# EVK-NORA-B2_SCHEM_0006_USBhub_FTDI.net
KiCad netlist of a schematic drawn in Altium Designer
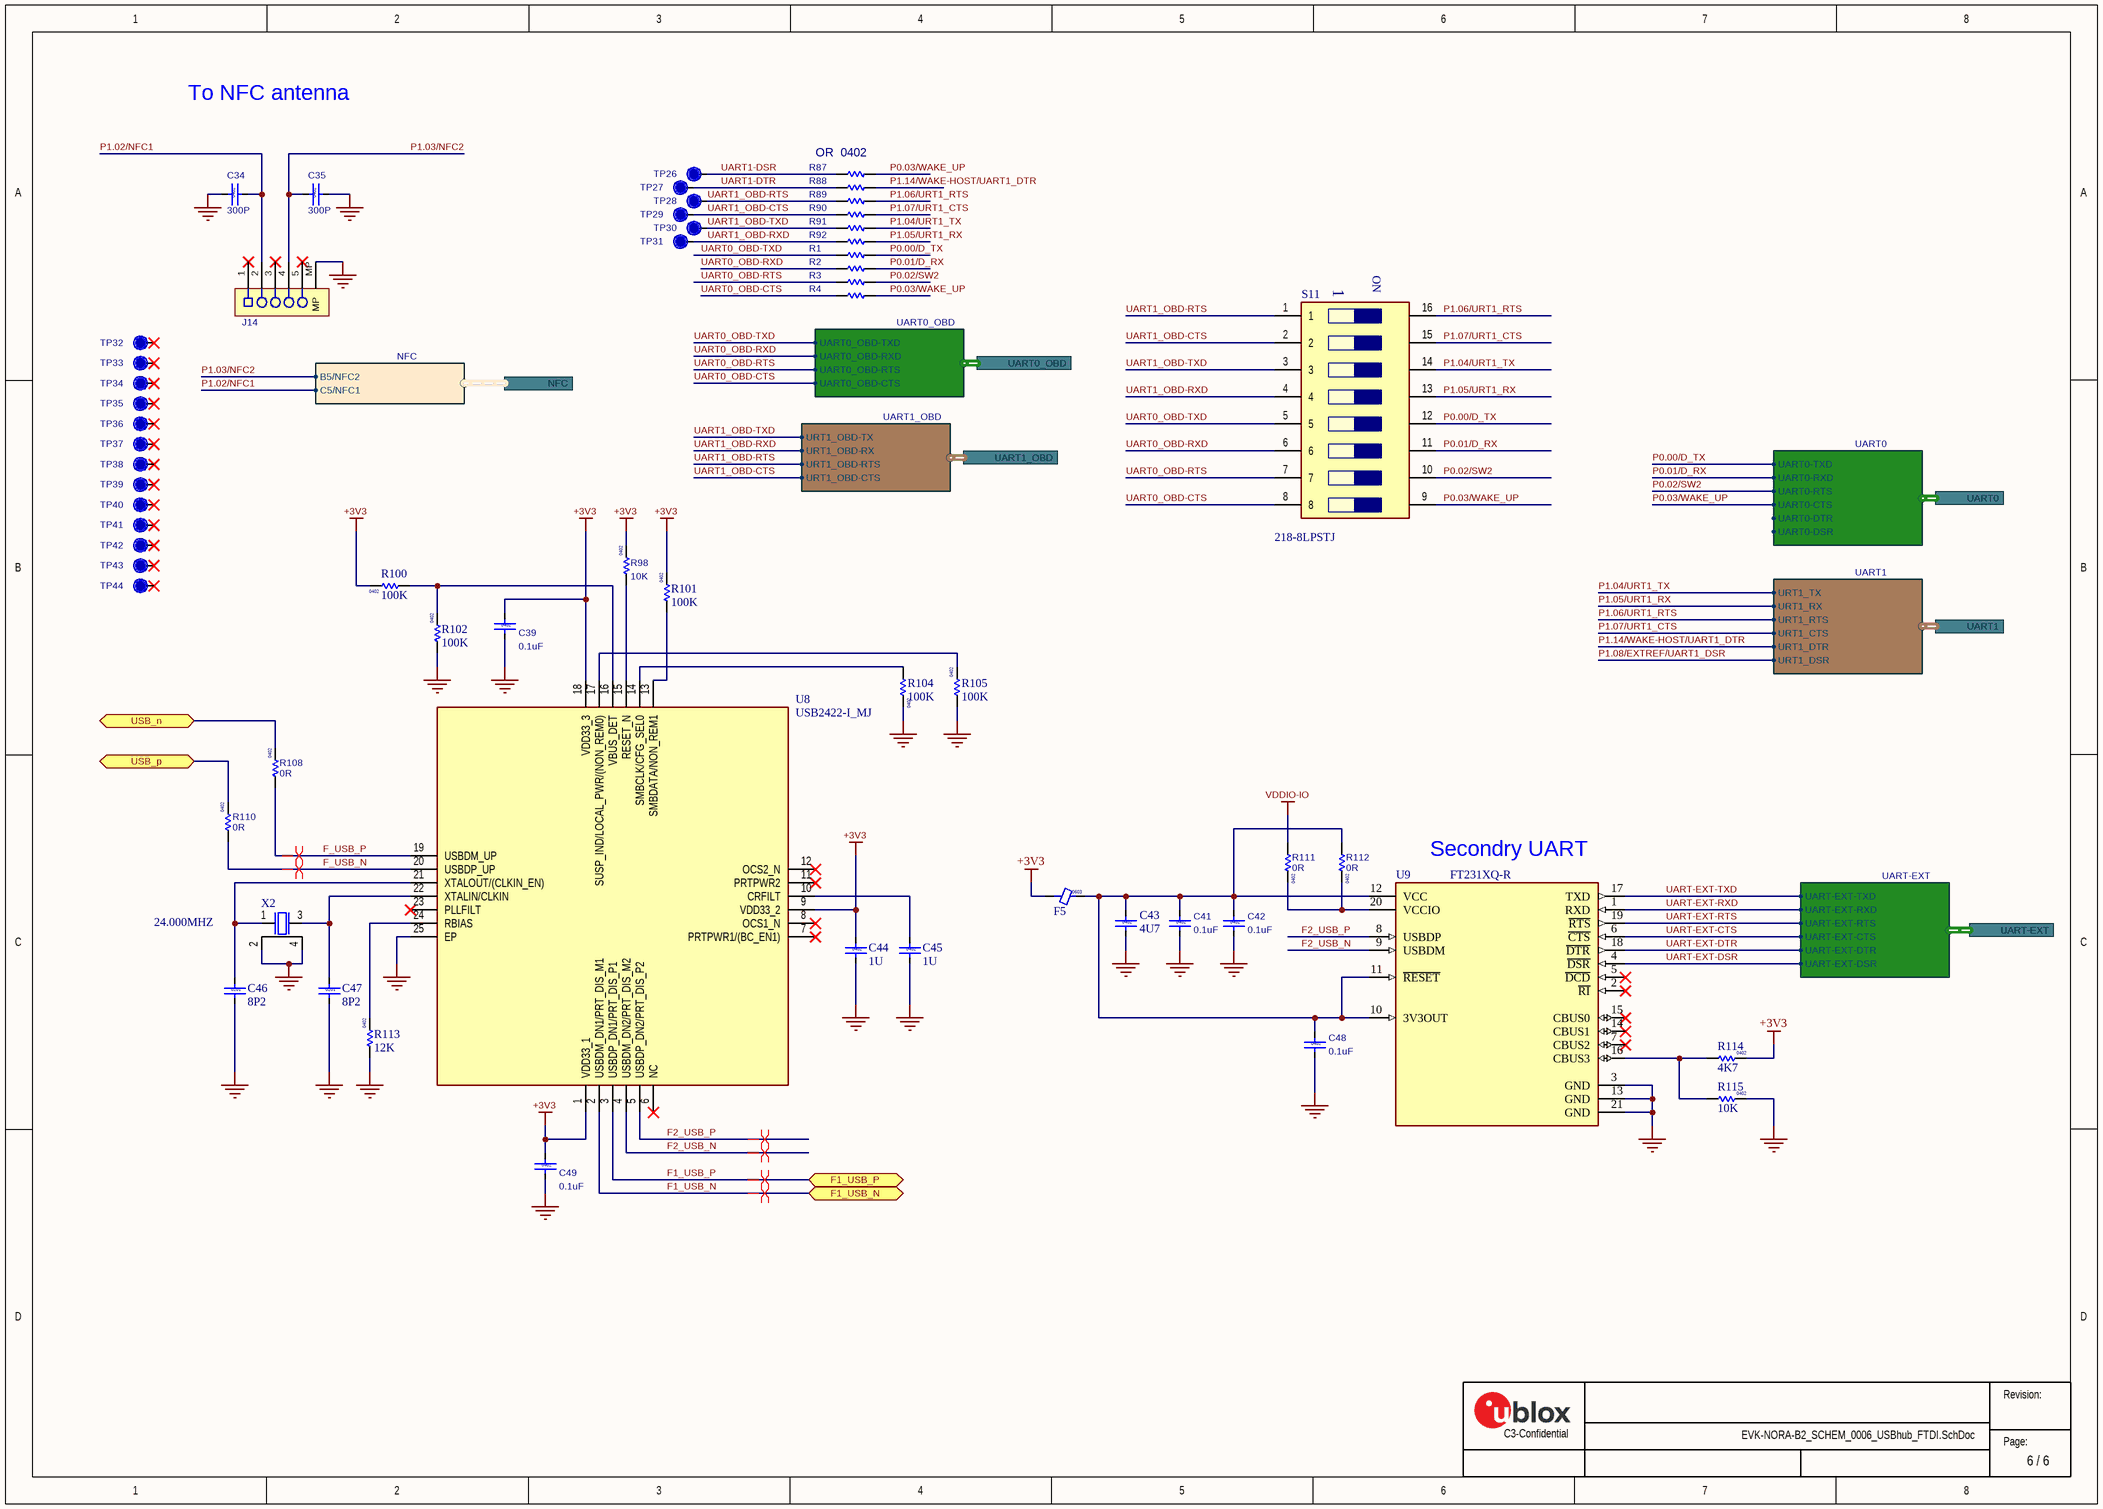
[diagram p0: EVK-NORA-B2_SCHEM_0006_USBhub_FTDI.SchDoc]

(export (version "E")
  (design (tool "Eeschema 10.0.6"))
  (components
    (comp (ref "C34")
      (value "300P")
      (footprint "Cap 0402 HD")
      (description "CAP CER C0G 0402 300P 50V")
      (fields
        (field (name "SIZE") "0402")
        (field (name "PART NUMBER") "UBXH01-0000594")
        (field (name "MANUFACTURER") "Murata Manufacturing Company, Ltd.")
        (field (name "EDITOR") "eric.moog")
      )
      (libsource (lib "UBX_Parts_DB_Lib") (part "Cap Chip"))
    )
    (comp (ref "C35")
      (value "300P")
      (footprint "Cap 0402 HD")
      (description "CAP CER C0G 0402 300P 50V")
      (fields
        (field (name "SIZE") "0402")
        (field (name "PART NUMBER") "UBXH01-0000594")
        (field (name "MANUFACTURER") "Murata Manufacturing Company, Ltd.")
        (field (name "EDITOR") "eric.moog")
      )
      (libsource (lib "UBX_Parts_DB_Lib") (part "Cap Chip"))
    )
    (comp (ref "C39")
      (value "0.1uF")
      (footprint "Cap 0402 HD")
      (description "Cap, Ceramic 0.1uF 10V 10% X5R 0402")
      (fields
        (field (name "SIZE") "0402")
        (field (name "PART NUMBER") "120-00016")
        (field (name "MANUFACTURER") "Murata Electronics North America")
      )
      (libsource (lib "Arena_Parts_DB_Lib") (part "Cap Chip"))
    )
    (comp (ref "C41")
      (value "0.1uF")
      (footprint "Cap 0402 HD")
      (description "Cap, Ceramic 0.1uF 10V 10% X5R 0402")
      (fields
        (field (name "SIZE") "0402")
        (field (name "PART NUMBER") "120-00016")
        (field (name "MANUFACTURER") "Murata Electronics North America")
      )
      (libsource (lib "Arena_Parts_DB_Lib") (part "Cap Chip"))
    )
    (comp (ref "C42")
      (value "0.1uF")
      (footprint "Cap 0402 HD")
      (description "Cap, Ceramic 0.1uF 10V 10% X5R 0402")
      (fields
        (field (name "SIZE") "0402")
        (field (name "PART NUMBER") "120-00016")
        (field (name "MANUFACTURER") "Murata Electronics North America")
      )
      (libsource (lib "Arena_Parts_DB_Lib") (part "Cap Chip"))
    )
    (comp (ref "C43")
      (value "4U7")
      (footprint "Cap 0402 HD")
      (description "CAP CER X5R 0402 4U7 20% 10V")
      (fields
        (field (name "SIZE") "0402")
        (field (name "PART NUMBER") "UBXH01-0000243")
        (field (name "TOLERANCE") "20%")
        (field (name "EDITOR") "martin.pilik")
        (field (name "RELEASED BY") "fabrice.bret-dibat")
      )
      (libsource (lib "UBX_Parts_DB_Lib") (part "Cap Chip"))
    )
    (comp (ref "C44")
      (value "1U")
      (footprint "Cap 0402 HD")
      (description "CAP CER X5R 0402 1U 10% 10V")
      (fields
        (field (name "SIZE") "0402")
        (field (name "PART NUMBER") "UBXH01-0000248")
        (field (name "TOLERANCE") "10%")
        (field (name "EDITOR") "michael.hein")
        (field (name "RELEASED BY") "igor.shevchenko")
      )
      (libsource (lib "UBX_Parts_DB_Lib") (part "Cap Chip"))
    )
    (comp (ref "C45")
      (value "1U")
      (footprint "Cap 0402 HD")
      (description "CAP CER X5R 0402 1U 10% 10V")
      (fields
        (field (name "SIZE") "0402")
        (field (name "PART NUMBER") "UBXH01-0000248")
        (field (name "TOLERANCE") "10%")
        (field (name "EDITOR") "michael.hein")
        (field (name "RELEASED BY") "igor.shevchenko")
      )
      (libsource (lib "UBX_Parts_DB_Lib") (part "Cap Chip"))
    )
    (comp (ref "C46")
      (value "8P2")
      (footprint "Cap 0201 HD")
      (description "CAP CER C0G 0201 8P2 +/-0.5P 25V")
      (fields
        (field (name "SIZE") "0201")
        (field (name "PART NUMBER") "UBXH01-0013002")
        (field (name "TOLERANCE") "+/-0.5P")
        (field (name "EDITOR") "roland.rust")
        (field (name "RELEASED BY") "roland.rust")
      )
      (libsource (lib "UBX_Parts_DB_Lib") (part "Cap Chip"))
    )
    (comp (ref "C47")
      (value "8P2")
      (footprint "Cap 0201 HD")
      (description "CAP CER C0G 0201 8P2 +/-0.5P 25V")
      (fields
        (field (name "SIZE") "0201")
        (field (name "PART NUMBER") "UBXH01-0013002")
        (field (name "TOLERANCE") "+/-0.5P")
        (field (name "EDITOR") "roland.rust")
        (field (name "RELEASED BY") "roland.rust")
      )
      (libsource (lib "UBX_Parts_DB_Lib") (part "Cap Chip"))
    )
    (comp (ref "C48")
      (value "0.1uF")
      (footprint "Cap 0402 HD")
      (description "Cap, Ceramic 0.1uF 10V 10% X5R 0402")
      (fields
        (field (name "SIZE") "0402")
        (field (name "PART NUMBER") "120-00016")
        (field (name "MANUFACTURER") "Murata Electronics North America")
      )
      (libsource (lib "Arena_Parts_DB_Lib") (part "Cap Chip"))
    )
    (comp (ref "C49")
      (value "0.1uF")
      (footprint "Cap 0402 HD")
      (description "Cap, Ceramic 0.1uF 10V 10% X5R 0402")
      (fields
        (field (name "SIZE") "0402")
        (field (name "PART NUMBER") "120-00016")
        (field (name "MANUFACTURER") "Murata Electronics North America")
      )
      (libsource (lib "Arena_Parts_DB_Lib") (part "Cap Chip"))
    )
    (comp (ref "F5")
      (value "UBXH08-0000001")
      (footprint "IND_0603_1750Lx950Wx1050H_600x800Pad_800G_FLX")
      (description "FERRITE BEAD 0603 600 OHM AT 100MHZ 600OHM 500mA")
      (fields
        (field (name "SIZE") "0603")
        (field (name "MANUFACTURER") "TDK Corporation")
        (field (name "EDITOR") "daniel.hurni")
        (field (name "RELEASED BY") "martin.frauchiger")
      )
      (libsource (lib "UBX_Parts_DB_Lib") (part "FB sm"))
    )
    (comp (ref "J14")
      (value "UBXH04-0000798")
      (footprint "AVX/Kyocera - 046284005001846")
      (description "0.50MM PITCH SMD RA FFC FPC CONN 5 -PIN 50V 400mA")
      (fields
        (field (name "VOLTAGE") "50V")
        (field (name "MANUFACTURER") "AVX")
        (field (name "EDITOR") "eric.moog")
      )
      (libsource (lib "UBX_Parts_DB_Lib") (part "CON-5Pin_1Row-046284005001846"))
    )
    (comp (ref "R1")
      (value "UBXH18-00030020R")
      (footprint "RES 0402 HD")
      (description "RES THICK FILM CHIP 0402 0R 0 100mW")
      (fields
        (field (name "PART NUMBER") "UBXH18-0003002")
        (field (name "TOLERANCE") "0")
        (field (name "EDITOR") "charlotte.biber")
        (field (name "RELEASED BY") "peter.mueller")
      )
      (libsource (lib "UBX_Parts_DB_Lib") (part "Res sm"))
    )
    (comp (ref "R2")
      (value "UBXH18-00030020R")
      (footprint "RES 0402 HD")
      (description "RES THICK FILM CHIP 0402 0R 0 100mW")
      (fields
        (field (name "PART NUMBER") "UBXH18-0003002")
        (field (name "TOLERANCE") "0")
        (field (name "EDITOR") "charlotte.biber")
        (field (name "RELEASED BY") "peter.mueller")
      )
      (libsource (lib "UBX_Parts_DB_Lib") (part "Res sm"))
    )
    (comp (ref "R3")
      (value "UBXH18-00030020R")
      (footprint "RES 0402 HD")
      (description "RES THICK FILM CHIP 0402 0R 0 100mW")
      (fields
        (field (name "PART NUMBER") "UBXH18-0003002")
        (field (name "TOLERANCE") "0")
        (field (name "EDITOR") "charlotte.biber")
        (field (name "RELEASED BY") "peter.mueller")
      )
      (libsource (lib "UBX_Parts_DB_Lib") (part "Res sm"))
    )
    (comp (ref "R4")
      (value "UBXH18-00030020R")
      (footprint "RES 0402 HD")
      (description "RES THICK FILM CHIP 0402 0R 0 100mW")
      (fields
        (field (name "PART NUMBER") "UBXH18-0003002")
        (field (name "TOLERANCE") "0")
        (field (name "EDITOR") "charlotte.biber")
        (field (name "RELEASED BY") "peter.mueller")
      )
      (libsource (lib "UBX_Parts_DB_Lib") (part "Res sm"))
    )
    (comp (ref "R87")
      (value "UBXH18-00030020R")
      (footprint "RES 0402 HD")
      (description "RES THICK FILM CHIP 0402 0R 0 100mW")
      (fields
        (field (name "PART NUMBER") "UBXH18-0003002")
        (field (name "TOLERANCE") "0")
        (field (name "EDITOR") "charlotte.biber")
        (field (name "RELEASED BY") "peter.mueller")
      )
      (libsource (lib "UBX_Parts_DB_Lib") (part "Res sm"))
    )
    (comp (ref "R88")
      (value "UBXH18-00030020R")
      (footprint "RES 0402 HD")
      (description "RES THICK FILM CHIP 0402 0R 0 100mW")
      (fields
        (field (name "PART NUMBER") "UBXH18-0003002")
        (field (name "TOLERANCE") "0")
        (field (name "EDITOR") "charlotte.biber")
        (field (name "RELEASED BY") "peter.mueller")
      )
      (libsource (lib "UBX_Parts_DB_Lib") (part "Res sm"))
    )
    (comp (ref "R89")
      (value "UBXH18-00030020R")
      (footprint "RES 0402 HD")
      (description "RES THICK FILM CHIP 0402 0R 0 100mW")
      (fields
        (field (name "PART NUMBER") "UBXH18-0003002")
        (field (name "TOLERANCE") "0")
        (field (name "EDITOR") "charlotte.biber")
        (field (name "RELEASED BY") "peter.mueller")
      )
      (libsource (lib "UBX_Parts_DB_Lib") (part "Res sm"))
    )
    (comp (ref "R90")
      (value "UBXH18-00030020R")
      (footprint "RES 0402 HD")
      (description "RES THICK FILM CHIP 0402 0R 0 100mW")
      (fields
        (field (name "PART NUMBER") "UBXH18-0003002")
        (field (name "TOLERANCE") "0")
        (field (name "EDITOR") "charlotte.biber")
        (field (name "RELEASED BY") "peter.mueller")
      )
      (libsource (lib "UBX_Parts_DB_Lib") (part "Res sm"))
    )
    (comp (ref "R91")
      (value "UBXH18-00030020R")
      (footprint "RES 0402 HD")
      (description "RES THICK FILM CHIP 0402 0R 0 100mW")
      (fields
        (field (name "PART NUMBER") "UBXH18-0003002")
        (field (name "TOLERANCE") "0")
        (field (name "EDITOR") "charlotte.biber")
        (field (name "RELEASED BY") "peter.mueller")
      )
      (libsource (lib "UBX_Parts_DB_Lib") (part "Res sm"))
    )
    (comp (ref "R92")
      (value "UBXH18-00030020R")
      (footprint "RES 0402 HD")
      (description "RES THICK FILM CHIP 0402 0R 0 100mW")
      (fields
        (field (name "PART NUMBER") "UBXH18-0003002")
        (field (name "TOLERANCE") "0")
        (field (name "EDITOR") "charlotte.biber")
        (field (name "RELEASED BY") "peter.mueller")
      )
      (libsource (lib "UBX_Parts_DB_Lib") (part "Res sm"))
    )
    (comp (ref "R98")
      (value "10K")
      (footprint "RES 0402 HD")
      (description "RES THICK FILM CHIP 0402 10K 1% 63mW")
      (fields
        (field (name "SIZE") "0402")
        (field (name "PART NUMBER") "UBXH18-0000065")
        (field (name "TOLERANCE") "1%")
        (field (name "EDITOR") "erian.bezhani")
        (field (name "RELEASED BY") "massimo.vlacci")
      )
      (libsource (lib "UBX_Parts_DB_Lib") (part "Res sm"))
    )
    (comp (ref "R100")
      (value "100K")
      (footprint "RES 0402 HD")
      (description "RES THICK FILM CHIP 0402 100K 1% 63mW")
      (fields
        (field (name "SIZE") "0402")
        (field (name "PART NUMBER") "UBXH18-0000005")
        (field (name "TOLERANCE") "1%")
        (field (name "EDITOR") "dario.antonaz")
        (field (name "RELEASED BY") "sandro.sestan")
      )
      (libsource (lib "UBX_Parts_DB_Lib") (part "Res sm"))
    )
    (comp (ref "R101")
      (value "100K")
      (footprint "RES 0402 HD")
      (description "RES THICK FILM CHIP 0402 100K 1% 63mW")
      (fields
        (field (name "SIZE") "0402")
        (field (name "PART NUMBER") "UBXH18-0000005")
        (field (name "TOLERANCE") "1%")
        (field (name "EDITOR") "dario.antonaz")
        (field (name "RELEASED BY") "sandro.sestan")
      )
      (libsource (lib "UBX_Parts_DB_Lib") (part "Res sm"))
    )
    (comp (ref "R102")
      (value "100K")
      (footprint "RES 0402 HD")
      (description "RES THICK FILM CHIP 0402 100K 1% 63mW")
      (fields
        (field (name "SIZE") "0402")
        (field (name "PART NUMBER") "UBXH18-0000005")
        (field (name "TOLERANCE") "1%")
        (field (name "EDITOR") "dario.antonaz")
        (field (name "RELEASED BY") "sandro.sestan")
      )
      (libsource (lib "UBX_Parts_DB_Lib") (part "Res sm"))
    )
    (comp (ref "R104")
      (value "100K")
      (footprint "RES 0402 HD")
      (description "RES THICK FILM CHIP 0402 100K 1% 63mW")
      (fields
        (field (name "SIZE") "0402")
        (field (name "PART NUMBER") "UBXH18-0000005")
        (field (name "TOLERANCE") "1%")
        (field (name "EDITOR") "dario.antonaz")
        (field (name "RELEASED BY") "sandro.sestan")
      )
      (libsource (lib "UBX_Parts_DB_Lib") (part "Res sm"))
    )
    (comp (ref "R105")
      (value "100K")
      (footprint "RES 0402 HD")
      (description "RES THICK FILM CHIP 0402 100K 1% 63mW")
      (fields
        (field (name "SIZE") "0402")
        (field (name "PART NUMBER") "UBXH18-0000005")
        (field (name "TOLERANCE") "1%")
        (field (name "EDITOR") "dario.antonaz")
        (field (name "RELEASED BY") "sandro.sestan")
      )
      (libsource (lib "UBX_Parts_DB_Lib") (part "Res sm"))
    )
    (comp (ref "R108")
      (value "0R")
      (footprint "RES 0402 HD")
      (description "RES THICK FILM CHIP 0402 0R 0 100mW")
      (fields
        (field (name "SIZE") "0402")
        (field (name "PART NUMBER") "UBXH18-0003002")
        (field (name "TOLERANCE") "0")
        (field (name "EDITOR") "charlotte.biber")
        (field (name "RELEASED BY") "peter.mueller")
      )
      (libsource (lib "UBX_Parts_DB_Lib") (part "Res sm"))
    )
    (comp (ref "R110")
      (value "0R")
      (footprint "RES 0402 HD")
      (description "RES THICK FILM CHIP 0402 0R 0 100mW")
      (fields
        (field (name "SIZE") "0402")
        (field (name "PART NUMBER") "UBXH18-0003002")
        (field (name "TOLERANCE") "0")
        (field (name "EDITOR") "charlotte.biber")
        (field (name "RELEASED BY") "peter.mueller")
      )
      (libsource (lib "UBX_Parts_DB_Lib") (part "Res sm"))
    )
    (comp (ref "R111")
      (value "0R")
      (footprint "RES 0402 HD")
      (description "RES THICK FILM CHIP 0402 0R 0 100mW")
      (fields
        (field (name "SIZE") "0402")
        (field (name "PART NUMBER") "UBXH18-0003002")
        (field (name "TOLERANCE") "0")
        (field (name "EDITOR") "charlotte.biber")
        (field (name "RELEASED BY") "peter.mueller")
      )
      (libsource (lib "UBX_Parts_DB_Lib") (part "Res sm"))
    )
    (comp (ref "R112")
      (value "0R")
      (footprint "RES 0402 HD")
      (description "RES THICK FILM CHIP 0402 0R 0 100mW")
      (fields
        (field (name "SIZE") "0402")
        (field (name "PART NUMBER") "UBXH18-0003002")
        (field (name "TOLERANCE") "0")
        (field (name "EDITOR") "charlotte.biber")
        (field (name "RELEASED BY") "peter.mueller")
      )
      (libsource (lib "UBX_Parts_DB_Lib") (part "Res sm"))
    )
    (comp (ref "R113")
      (value "12K")
      (footprint "RES_0402_1100Lx600Wx400H_500x600Pad_400G_FLX")
      (description "RES THICK FILM CHIP 0402 12K 1% 62.5mW")
      (fields
        (field (name "SIZE") "0402")
        (field (name "PART NUMBER") "UBXH18-0000133")
        (field (name "TOLERANCE") "1%")
        (field (name "EDITOR") "pierpaolo.arban")
        (field (name "RELEASED BY") "dario.antonaz")
      )
      (libsource (lib "UBX_Parts_DB_Lib") (part "Res sm"))
    )
    (comp (ref "R114")
      (value "4K7")
      (footprint "RES_0402_1100Lx600Wx400H_500x600Pad_400G_FLX")
      (description "RES THICK FILM CHIP 0402 4K7 5% 100mW")
      (fields
        (field (name "SIZE") "0402")
        (field (name "PART NUMBER") "UBXH18-0008065")
        (field (name "TOLERANCE") "5%")
        (field (name "EDITOR") "martin.frauchiger")
        (field (name "RELEASED BY") "martin.frauchiger")
      )
      (libsource (lib "UBX_Parts_DB_Lib") (part "Res sm"))
    )
    (comp (ref "R115")
      (value "10K")
      (footprint "RES_0402_1100Lx600Wx400H_500x600Pad_400G_FLX")
      (description "RES THICK FILM CHIP 0402 10K 5% 100mW")
      (fields
        (field (name "SIZE") "0402")
        (field (name "PART NUMBER") "UBXH18-0008073")
        (field (name "TOLERANCE") "5%")
        (field (name "EDITOR") "martin.frauchiger")
        (field (name "RELEASED BY") "martin.frauchiger")
      )
      (libsource (lib "UBX_Parts_DB_Lib") (part "Res sm"))
    )
    (comp (ref "S11")
      (value "218-8LPSTJ")
      (footprint "2188LPSTJ")
      (description "Switch")
      (fields (field (name "MOUSER PART NUMBER") "774-2188LPSTJ"))
      (libsource (lib "SamacSys") (part "218-8LPSTJ"))
    )
    (comp (ref "TP26")
      (value "TP")
      (footprint "TP10R")
      (description "Testpoint, Round 1.0mm Dia")
      (fields
        (field (name "PART NUMBER") "TP10R")
        (field (name "ADDED BY") "Jeremy D")
        (field (name "CHECKED BY") "Paul B")
      )
      (libsource (lib "LEGACY_Rigado_AltiumLib") (part "TP_R"))
    )
    (comp (ref "TP27")
      (value "TP")
      (footprint "TP10R")
      (description "Testpoint, Round 1.0mm Dia")
      (fields
        (field (name "PART NUMBER") "TP10R")
        (field (name "ADDED BY") "Jeremy D")
        (field (name "CHECKED BY") "Paul B")
      )
      (libsource (lib "LEGACY_Rigado_AltiumLib") (part "TP_R"))
    )
    (comp (ref "TP28")
      (value "TP")
      (footprint "TP10R")
      (description "Testpoint, Round 1.0mm Dia")
      (fields
        (field (name "PART NUMBER") "TP10R")
        (field (name "ADDED BY") "Jeremy D")
        (field (name "CHECKED BY") "Paul B")
      )
      (libsource (lib "LEGACY_Rigado_AltiumLib") (part "TP_R"))
    )
    (comp (ref "TP29")
      (value "TP")
      (footprint "TP10R")
      (description "Testpoint, Round 1.0mm Dia")
      (fields
        (field (name "PART NUMBER") "TP10R")
        (field (name "ADDED BY") "Jeremy D")
        (field (name "CHECKED BY") "Paul B")
      )
      (libsource (lib "LEGACY_Rigado_AltiumLib") (part "TP_R"))
    )
    (comp (ref "TP30")
      (value "TP")
      (footprint "TP10R")
      (description "Testpoint, Round 1.0mm Dia")
      (fields
        (field (name "PART NUMBER") "TP10R")
        (field (name "ADDED BY") "Jeremy D")
        (field (name "CHECKED BY") "Paul B")
      )
      (libsource (lib "LEGACY_Rigado_AltiumLib") (part "TP_R"))
    )
    (comp (ref "TP31")
      (value "TP")
      (footprint "TP10R")
      (description "Testpoint, Round 1.0mm Dia")
      (fields
        (field (name "PART NUMBER") "TP10R")
        (field (name "ADDED BY") "Jeremy D")
        (field (name "CHECKED BY") "Paul B")
      )
      (libsource (lib "LEGACY_Rigado_AltiumLib") (part "TP_R"))
    )
    (comp (ref "TP32")
      (value "TP")
      (footprint "TP10R")
      (description "Testpoint, Round 1.0mm Dia")
      (fields
        (field (name "PART NUMBER") "TP10R")
        (field (name "ADDED BY") "Jeremy D")
        (field (name "CHECKED BY") "Paul B")
      )
      (libsource (lib "LEGACY_Rigado_AltiumLib") (part "TP_R"))
    )
    (comp (ref "TP33")
      (value "TP")
      (footprint "TP10R")
      (description "Testpoint, Round 1.0mm Dia")
      (fields
        (field (name "PART NUMBER") "TP10R")
        (field (name "ADDED BY") "Jeremy D")
        (field (name "CHECKED BY") "Paul B")
      )
      (libsource (lib "LEGACY_Rigado_AltiumLib") (part "TP_R"))
    )
    (comp (ref "TP34")
      (value "TP")
      (footprint "TP10R")
      (description "Testpoint, Round 1.0mm Dia")
      (fields
        (field (name "PART NUMBER") "TP10R")
        (field (name "ADDED BY") "Jeremy D")
        (field (name "CHECKED BY") "Paul B")
      )
      (libsource (lib "LEGACY_Rigado_AltiumLib") (part "TP_R"))
    )
    (comp (ref "TP35")
      (value "TP")
      (footprint "TP10R")
      (description "Testpoint, Round 1.0mm Dia")
      (fields
        (field (name "PART NUMBER") "TP10R")
        (field (name "ADDED BY") "Jeremy D")
        (field (name "CHECKED BY") "Paul B")
      )
      (libsource (lib "LEGACY_Rigado_AltiumLib") (part "TP_R"))
    )
    (comp (ref "TP36")
      (value "TP")
      (footprint "TP10R")
      (description "Testpoint, Round 1.0mm Dia")
      (fields
        (field (name "PART NUMBER") "TP10R")
        (field (name "ADDED BY") "Jeremy D")
        (field (name "CHECKED BY") "Paul B")
      )
      (libsource (lib "LEGACY_Rigado_AltiumLib") (part "TP_R"))
    )
    (comp (ref "TP37")
      (value "TP")
      (footprint "TP10R")
      (description "Testpoint, Round 1.0mm Dia")
      (fields
        (field (name "PART NUMBER") "TP10R")
        (field (name "ADDED BY") "Jeremy D")
        (field (name "CHECKED BY") "Paul B")
      )
      (libsource (lib "LEGACY_Rigado_AltiumLib") (part "TP_R"))
    )
    (comp (ref "TP38")
      (value "TP")
      (footprint "TP10R")
      (description "Testpoint, Round 1.0mm Dia")
      (fields
        (field (name "PART NUMBER") "TP10R")
        (field (name "ADDED BY") "Jeremy D")
        (field (name "CHECKED BY") "Paul B")
      )
      (libsource (lib "LEGACY_Rigado_AltiumLib") (part "TP_R"))
    )
    (comp (ref "TP39")
      (value "TP")
      (footprint "TP10R")
      (description "Testpoint, Round 1.0mm Dia")
      (fields
        (field (name "PART NUMBER") "TP10R")
        (field (name "ADDED BY") "Jeremy D")
        (field (name "CHECKED BY") "Paul B")
      )
      (libsource (lib "LEGACY_Rigado_AltiumLib") (part "TP_R"))
    )
    (comp (ref "TP40")
      (value "TP")
      (footprint "TP10R")
      (description "Testpoint, Round 1.0mm Dia")
      (fields
        (field (name "PART NUMBER") "TP10R")
        (field (name "ADDED BY") "Jeremy D")
        (field (name "CHECKED BY") "Paul B")
      )
      (libsource (lib "LEGACY_Rigado_AltiumLib") (part "TP_R"))
    )
    (comp (ref "TP41")
      (value "TP")
      (footprint "TP10R")
      (description "Testpoint, Round 1.0mm Dia")
      (fields
        (field (name "PART NUMBER") "TP10R")
        (field (name "ADDED BY") "Jeremy D")
        (field (name "CHECKED BY") "Paul B")
      )
      (libsource (lib "LEGACY_Rigado_AltiumLib") (part "TP_R"))
    )
    (comp (ref "TP42")
      (value "TP")
      (footprint "TP10R")
      (description "Testpoint, Round 1.0mm Dia")
      (fields
        (field (name "PART NUMBER") "TP10R")
        (field (name "ADDED BY") "Jeremy D")
        (field (name "CHECKED BY") "Paul B")
      )
      (libsource (lib "LEGACY_Rigado_AltiumLib") (part "TP_R"))
    )
    (comp (ref "TP43")
      (value "TP")
      (footprint "TP10R")
      (description "Testpoint, Round 1.0mm Dia")
      (fields
        (field (name "PART NUMBER") "TP10R")
        (field (name "ADDED BY") "Jeremy D")
        (field (name "CHECKED BY") "Paul B")
      )
      (libsource (lib "LEGACY_Rigado_AltiumLib") (part "TP_R"))
    )
    (comp (ref "TP44")
      (value "TP")
      (footprint "TP10R")
      (description "Testpoint, Round 1.0mm Dia")
      (fields
        (field (name "PART NUMBER") "TP10R")
        (field (name "ADDED BY") "Jeremy D")
        (field (name "CHECKED BY") "Paul B")
      )
      (libsource (lib "LEGACY_Rigado_AltiumLib") (part "TP_R"))
    )
    (comp (ref "U8")
      (value "USB2422-I_MJ")
      (footprint "SamacSys:QFN50P400X400X100-25N-D")
      (description "Integrated Circuit")
      (fields
        (field (name "MANUFACTURER_PART_NUMBER") "USB2422-I/MJ")
        (field (name "MOUSER PART NUMBER") "579-USB2422-I/MJ")
      )
      (libsource (lib "*") (part "USB2422-I_MJ"))
    )
    (comp (ref "U9")
      (value "FT231XQ-R")
      (footprint "QFN_5x5_FT231XQ")
      (description "FTDI USB TO SERIAL FULL UART INTERFACE QFN20")
      (fields
        (field (name "PART NUMBER") "UBXH10-0000054")
        (field (name "MANUFACTURER") "FTDI Future Technology Devices International")
        (field (name "EDITOR") "adam.johansson")
      )
      (libsource (lib "UBX_Parts_DB_Lib") (part "FT231XQ-R"))
    )
    (comp (ref "X2")
      (value "24.000MHZ")
      (footprint "XTAL_2016_HD")
      (description "CRYSTAL CL=8PF EPSON 2.0X1.6MM 24.000MHZ 30PPM")
      (fields
        (field (name "PART NUMBER") "UBXH21-0000066")
        (field (name "TOLERANCE") "30PPM")
        (field (name "EDITOR") "adam.johansson")
        (field (name "RELEASED BY") "olof.viklund")
      )
      (libsource (lib "UBX_Parts_DB_Lib") (part "XTAL_4Pin"))
    )
  )
  (nets
    (net (code "7") (name "+3V3") (class "Default")
      (node (ref "C39") (pin "1") (pinfunction "1_1") (pintype "passive"))
      (node (ref "C44") (pin "1") (pinfunction "1_1") (pintype "passive"))
      (node (ref "C49") (pin "1") (pinfunction "1_1") (pintype "passive"))
      (node (ref "F5") (pin "1") (pinfunction "1_1") (pintype "passive"))
      (node (ref "R100") (pin "2") (pinfunction "2_2") (pintype "passive"))
      (node (ref "R101") (pin "2") (pinfunction "2_2") (pintype "passive"))
      (node (ref "R114") (pin "2") (pinfunction "2_2") (pintype "passive"))
      (node (ref "R98") (pin "2") (pinfunction "2_2") (pintype "passive"))
      (node (ref "U8") (pin "1") (pinfunction "VDD33_1_1") (pintype "passive"))
      (node (ref "U8") (pin "18") (pinfunction "VDD33_3_18") (pintype "passive"))
      (node (ref "U8") (pin "9") (pinfunction "VDD33_2_9") (pintype "passive"))
    )
    (net (code "8") (name "/F1_USB_N") (class "Default")
      (node (ref "U8") (pin "2") (pinfunction "USBDM_DN1/PRT_DIS_M1_2") (pintype "passive"))
    )
    (net (code "9") (name "/F1_USB_P") (class "Default")
      (node (ref "U8") (pin "3") (pinfunction "USBDP_DN1/PRT_DIS_P1_3") (pintype "passive"))
    )
    (net (code "10") (name "/F2_USB_N") (class "Default")
      (node (ref "U8") (pin "4") (pinfunction "USBDM_DN2/PRT_DIS_M2_4") (pintype "passive"))
      (node (ref "U9") (pin "9") (pinfunction "USBDM_9") (pintype "input"))
    )
    (net (code "11") (name "/F2_USB_P") (class "Default")
      (node (ref "U8") (pin "5") (pinfunction "USBDP_DN2/PRT_DIS_P2_5") (pintype "passive"))
      (node (ref "U9") (pin "8") (pinfunction "USBDP_8") (pintype "input"))
    )
    (net (code "12") (name "/F_USB_N") (class "Default")
      (node (ref "R110") (pin "1") (pinfunction "1_1") (pintype "passive"))
      (node (ref "U8") (pin "20") (pinfunction "USBDP_UP_20") (pintype "passive"))
    )
    (net (code "13") (name "/F_USB_P") (class "Default")
      (node (ref "R108") (pin "1") (pinfunction "1_1") (pintype "passive"))
      (node (ref "U8") (pin "19") (pinfunction "USBDM_UP_19") (pintype "passive"))
    )
    (net (code "14") (name "/P0.00{slash}D_TX") (class "Default")
      (node (ref "R1") (pin "2") (pinfunction "2_2") (pintype "passive"))
      (node (ref "S11") (pin "12") (pintype "passive"))
    )
    (net (code "15") (name "/P0.01{slash}D_RX") (class "Default")
      (node (ref "R2") (pin "2") (pinfunction "2_2") (pintype "passive"))
      (node (ref "S11") (pin "11") (pintype "passive"))
    )
    (net (code "16") (name "/P0.02{slash}SW2") (class "Default")
      (node (ref "R3") (pin "2") (pinfunction "2_2") (pintype "passive"))
      (node (ref "S11") (pin "10") (pintype "passive"))
    )
    (net (code "17") (name "/P0.03{slash}WAKE_UP") (class "Default")
      (node (ref "R4") (pin "2") (pinfunction "2_2") (pintype "passive"))
      (node (ref "R87") (pin "2") (pinfunction "2_2") (pintype "passive"))
      (node (ref "S11") (pin "9") (pintype "passive"))
    )
    (net (code "18") (name "/P1.02{slash}NFC1") (class "Default")
      (node (ref "C34") (pin "2") (pinfunction "2_2") (pintype "passive"))
      (node (ref "J14") (pin "2") (pinfunction "2_2") (pintype "passive"))
    )
    (net (code "19") (name "/P1.03{slash}NFC2") (class "Default")
      (node (ref "C35") (pin "1") (pinfunction "1_1") (pintype "passive"))
      (node (ref "J14") (pin "4") (pinfunction "4_4") (pintype "passive"))
    )
    (net (code "20") (name "/P1.04{slash}URT1_TX") (class "Default")
      (node (ref "R91") (pin "2") (pinfunction "2_2") (pintype "passive"))
      (node (ref "S11") (pin "14") (pintype "passive"))
    )
    (net (code "21") (name "/P1.05{slash}URT1_RX") (class "Default")
      (node (ref "R92") (pin "2") (pinfunction "2_2") (pintype "passive"))
      (node (ref "S11") (pin "13") (pintype "passive"))
    )
    (net (code "22") (name "/P1.06{slash}URT1_RTS") (class "Default")
      (node (ref "R89") (pin "2") (pinfunction "2_2") (pintype "passive"))
      (node (ref "S11") (pin "16") (pintype "passive"))
    )
    (net (code "23") (name "/P1.07{slash}URT1_CTS") (class "Default")
      (node (ref "R90") (pin "2") (pinfunction "2_2") (pintype "passive"))
      (node (ref "S11") (pin "15") (pintype "passive"))
    )
    (net (code "25") (name "/P1.14{slash}WAKE-HOST{slash}UART1_DTR") (class "Default")
      (node (ref "R88") (pin "2") (pinfunction "2_2") (pintype "passive"))
    )
    (net (code "26") (name "/UART-EXT-CTS") (class "Default")
      (node (ref "U9") (pin "6") (pinfunction "~{CTS}_6") (pintype "input"))
    )
    (net (code "27") (name "/UART-EXT-DSR") (class "Default")
      (node (ref "U9") (pin "4") (pinfunction "~{DSR}_4") (pintype "input"))
    )
    (net (code "28") (name "/UART-EXT-DTR") (class "Default")
      (node (ref "U9") (pin "18") (pinfunction "~{DTR}_18") (pintype "output"))
    )
    (net (code "29") (name "/UART-EXT-RTS") (class "Default")
      (node (ref "U9") (pin "19") (pinfunction "~{RTS}_19") (pintype "output"))
    )
    (net (code "30") (name "/UART-EXT-RXD") (class "Default")
      (node (ref "U9") (pin "1") (pinfunction "RXD_1") (pintype "input"))
    )
    (net (code "31") (name "/UART-EXT-TXD") (class "Default")
      (node (ref "U9") (pin "17") (pinfunction "TXD_17") (pintype "output"))
    )
    (net (code "32") (name "/UART0_OBD-CTS") (class "Default")
      (node (ref "R4") (pin "1") (pinfunction "1_1") (pintype "passive"))
      (node (ref "S11") (pin "8") (pinfunction "8_8") (pintype "passive"))
    )
    (net (code "33") (name "/UART0_OBD-RTS") (class "Default")
      (node (ref "R3") (pin "1") (pinfunction "1_1") (pintype "passive"))
      (node (ref "S11") (pin "7") (pinfunction "7_7") (pintype "passive"))
    )
    (net (code "34") (name "/UART0_OBD-RXD") (class "Default")
      (node (ref "R2") (pin "1") (pinfunction "1_1") (pintype "passive"))
      (node (ref "S11") (pin "6") (pinfunction "6_6") (pintype "passive"))
    )
    (net (code "35") (name "/UART0_OBD-TXD") (class "Default")
      (node (ref "R1") (pin "1") (pinfunction "1_1") (pintype "passive"))
      (node (ref "S11") (pin "5") (pinfunction "5_5") (pintype "passive"))
    )
    (net (code "36") (name "/UART1-DSR") (class "Default")
      (node (ref "R87") (pin "1") (pinfunction "1_1") (pintype "passive"))
      (node (ref "TP27") (pin "1") (pintype "passive"))
    )
    (net (code "37") (name "/UART1-DTR") (class "Default")
      (node (ref "R88") (pin "1") (pinfunction "1_1") (pintype "passive"))
      (node (ref "TP26") (pin "1") (pintype "passive"))
    )
    (net (code "38") (name "/UART1_OBD-CTS") (class "Default")
      (node (ref "R90") (pin "1") (pinfunction "1_1") (pintype "passive"))
      (node (ref "S11") (pin "2") (pinfunction "2_2") (pintype "passive"))
      (node (ref "TP29") (pin "1") (pintype "passive"))
    )
    (net (code "39") (name "/UART1_OBD-RTS") (class "Default")
      (node (ref "R89") (pin "1") (pinfunction "1_1") (pintype "passive"))
      (node (ref "S11") (pin "1") (pinfunction "1_1") (pintype "passive"))
      (node (ref "TP28") (pin "1") (pintype "passive"))
    )
    (net (code "40") (name "/UART1_OBD-RXD") (class "Default")
      (node (ref "R92") (pin "1") (pinfunction "1_1") (pintype "passive"))
      (node (ref "S11") (pin "4") (pinfunction "4_4") (pintype "passive"))
      (node (ref "TP31") (pin "1") (pintype "passive"))
    )
    (net (code "41") (name "/UART1_OBD-TXD") (class "Default")
      (node (ref "R91") (pin "1") (pinfunction "1_1") (pintype "passive"))
      (node (ref "S11") (pin "3") (pinfunction "3_3") (pintype "passive"))
      (node (ref "TP30") (pin "1") (pintype "passive"))
    )
    (net (code "42") (name "/USB_n") (class "Default")
      (node (ref "R108") (pin "2") (pinfunction "2_2") (pintype "passive"))
    )
    (net (code "43") (name "/USB_p") (class "Default")
      (node (ref "R110") (pin "2") (pinfunction "2_2") (pintype "passive"))
    )
    (net (code "50") (name "GND") (class "Default")
      (node (ref "C34") (pin "1") (pinfunction "1_1") (pintype "passive"))
      (node (ref "C35") (pin "2") (pinfunction "2_2") (pintype "passive"))
      (node (ref "C39") (pin "2") (pinfunction "2_2") (pintype "passive"))
      (node (ref "C41") (pin "2") (pinfunction "2_2") (pintype "passive"))
      (node (ref "C42") (pin "2") (pinfunction "2_2") (pintype "passive"))
      (node (ref "C43") (pin "2") (pinfunction "2_2") (pintype "passive"))
      (node (ref "C44") (pin "2") (pinfunction "2_2") (pintype "passive"))
      (node (ref "C45") (pin "2") (pinfunction "2_2") (pintype "passive"))
      (node (ref "C46") (pin "2") (pinfunction "2_2") (pintype "passive"))
      (node (ref "C47") (pin "2") (pinfunction "2_2") (pintype "passive"))
      (node (ref "C48") (pin "2") (pinfunction "2_2") (pintype "passive"))
      (node (ref "C49") (pin "2") (pinfunction "2_2") (pintype "passive"))
      (node (ref "J14") (pin "MP") (pinfunction "MP_MP") (pintype "passive"))
      (node (ref "R102") (pin "1") (pinfunction "1_1") (pintype "passive"))
      (node (ref "R104") (pin "2") (pinfunction "2_2") (pintype "passive"))
      (node (ref "R105") (pin "1") (pinfunction "1_1") (pintype "passive"))
      (node (ref "R113") (pin "1") (pinfunction "1_1") (pintype "passive"))
      (node (ref "R115") (pin "2") (pinfunction "2_2") (pintype "passive"))
      (node (ref "U8") (pin "25") (pinfunction "EP_25") (pintype "passive"))
      (node (ref "U9") (pin "13") (pinfunction "GND_13") (pintype "power_in"))
      (node (ref "U9") (pin "21") (pinfunction "GND_21") (pintype "power_in"))
      (node (ref "U9") (pin "3") (pinfunction "GND_3") (pintype "power_in"))
      (node (ref "X2") (pin "2") (pintype "passive"))
      (node (ref "X2") (pin "4") (pintype "passive"))
    )
    (net (code "51") (name "Net-(U8-CRFILT)") (class "Default")
      (node (ref "C45") (pin "1") (pinfunction "1_1") (pintype "passive"))
      (node (ref "U8") (pin "10") (pinfunction "CRFILT_10") (pintype "passive"))
    )
    (net (code "52") (name "Net-(U8-RBIAS)") (class "Default")
      (node (ref "R113") (pin "2") (pinfunction "2_2") (pintype "passive"))
      (node (ref "U8") (pin "24") (pinfunction "RBIAS_24") (pintype "passive"))
    )
    (net (code "53") (name "Net-(U8-RESET_N)") (class "Default")
      (node (ref "R98") (pin "1") (pinfunction "1_1") (pintype "passive"))
      (node (ref "U8") (pin "15") (pinfunction "RESET_N_15") (pintype "passive"))
    )
    (net (code "54") (name "Net-(U8-SMBCLK{slash}CFG_SEL0)") (class "Default")
      (node (ref "R104") (pin "1") (pinfunction "1_1") (pintype "passive"))
      (node (ref "U8") (pin "14") (pinfunction "SMBCLK/CFG_SEL0_14") (pintype "passive"))
    )
    (net (code "55") (name "Net-(U8-SMBDATA{slash}NON_REM1)") (class "Default")
      (node (ref "R101") (pin "1") (pinfunction "1_1") (pintype "passive"))
      (node (ref "U8") (pin "13") (pinfunction "SMBDATA/NON_REM1_13") (pintype "passive"))
    )
    (net (code "56") (name "Net-(U8-SUSP_IND{slash}LOCAL_PWR{slash}(NON_REM0))") (class "Default")
      (node (ref "R105") (pin "2") (pinfunction "2_2") (pintype "passive"))
      (node (ref "U8") (pin "17") (pinfunction "SUSP_IND/LOCAL_PWR/(NON_REM0)_17") (pintype "passive"))
    )
    (net (code "57") (name "Net-(U8-VBUS_DET)") (class "Default")
      (node (ref "R100") (pin "1") (pinfunction "1_1") (pintype "passive"))
      (node (ref "R102") (pin "2") (pinfunction "2_2") (pintype "passive"))
      (node (ref "U8") (pin "16") (pinfunction "VBUS_DET_16") (pintype "passive"))
    )
    (net (code "58") (name "Net-(U8-XTALIN{slash}CLKIN)") (class "Default")
      (node (ref "C47") (pin "1") (pinfunction "1_1") (pintype "passive"))
      (node (ref "U8") (pin "22") (pinfunction "XTALIN/CLKIN_22") (pintype "passive"))
      (node (ref "X2") (pin "3") (pintype "passive"))
    )
    (net (code "59") (name "Net-(U8-XTALOUT{slash}(CLKIN_EN))") (class "Default")
      (node (ref "C46") (pin "1") (pinfunction "1_1") (pintype "passive"))
      (node (ref "U8") (pin "21") (pinfunction "XTALOUT/(CLKIN_EN)_21") (pintype "passive"))
      (node (ref "X2") (pin "1") (pintype "passive"))
    )
    (net (code "60") (name "Net-(U9-3V3OUT)") (class "Default")
      (node (ref "C41") (pin "1") (pinfunction "1_1") (pintype "passive"))
      (node (ref "C42") (pin "1") (pinfunction "1_1") (pintype "passive"))
      (node (ref "C43") (pin "1") (pinfunction "1_1") (pintype "passive"))
      (node (ref "C48") (pin "1") (pinfunction "1_1") (pintype "passive"))
      (node (ref "F5") (pin "2") (pinfunction "2_2") (pintype "passive"))
      (node (ref "R112") (pin "1") (pinfunction "1_1") (pintype "passive"))
      (node (ref "U9") (pin "10") (pinfunction "3V3OUT_10") (pintype "input"))
      (node (ref "U9") (pin "11") (pinfunction "~{RESET}_11") (pintype "input"))
      (node (ref "U9") (pin "12") (pinfunction "VCC_12") (pintype "power_in"))
    )
    (net (code "61") (name "Net-(U9-CBUS3)") (class "Default")
      (node (ref "R114") (pin "1") (pinfunction "1_1") (pintype "passive"))
      (node (ref "R115") (pin "1") (pinfunction "1_1") (pintype "passive"))
      (node (ref "U9") (pin "16") (pinfunction "CBUS3_16") (pintype "bidirectional"))
    )
    (net (code "62") (name "Net-(U9-VCCIO)") (class "Default")
      (node (ref "R111") (pin "2") (pinfunction "2_2") (pintype "passive"))
      (node (ref "R112") (pin "2") (pinfunction "2_2") (pintype "passive"))
      (node (ref "U9") (pin "20") (pinfunction "VCCIO_20") (pintype "power_in"))
    )
    (net (code "63") (name "VDDIO-IO") (class "Default")
      (node (ref "R111") (pin "1") (pinfunction "1_1") (pintype "passive"))
    )
    (net (code "64") (name "unconnected-(J14-Pad1)") (class "Default")
      (node (ref "J14") (pin "1") (pinfunction "1_1") (pintype "passive+no_connect"))
    )
    (net (code "65") (name "unconnected-(J14-Pad3)") (class "Default")
      (node (ref "J14") (pin "3") (pinfunction "3_3") (pintype "passive+no_connect"))
    )
    (net (code "66") (name "unconnected-(J14-Pad5)") (class "Default")
      (node (ref "J14") (pin "5") (pinfunction "5_5") (pintype "passive+no_connect"))
    )
    (net (code "67") (name "unconnected-(TP32-Pad1)") (class "Default")
      (node (ref "TP32") (pin "1") (pintype "passive+no_connect"))
    )
    (net (code "68") (name "unconnected-(TP33-Pad1)") (class "Default")
      (node (ref "TP33") (pin "1") (pintype "passive+no_connect"))
    )
    (net (code "69") (name "unconnected-(TP34-Pad1)") (class "Default")
      (node (ref "TP34") (pin "1") (pintype "passive+no_connect"))
    )
    (net (code "70") (name "unconnected-(TP35-Pad1)") (class "Default")
      (node (ref "TP35") (pin "1") (pintype "passive+no_connect"))
    )
    (net (code "71") (name "unconnected-(TP36-Pad1)") (class "Default")
      (node (ref "TP36") (pin "1") (pintype "passive+no_connect"))
    )
    (net (code "72") (name "unconnected-(TP37-Pad1)") (class "Default")
      (node (ref "TP37") (pin "1") (pintype "passive+no_connect"))
    )
    (net (code "73") (name "unconnected-(TP38-Pad1)") (class "Default")
      (node (ref "TP38") (pin "1") (pintype "passive+no_connect"))
    )
    (net (code "74") (name "unconnected-(TP39-Pad1)") (class "Default")
      (node (ref "TP39") (pin "1") (pintype "passive+no_connect"))
    )
    (net (code "75") (name "unconnected-(TP40-Pad1)") (class "Default")
      (node (ref "TP40") (pin "1") (pintype "passive+no_connect"))
    )
    (net (code "76") (name "unconnected-(TP41-Pad1)") (class "Default")
      (node (ref "TP41") (pin "1") (pintype "passive+no_connect"))
    )
    (net (code "77") (name "unconnected-(TP42-Pad1)") (class "Default")
      (node (ref "TP42") (pin "1") (pintype "passive+no_connect"))
    )
    (net (code "78") (name "unconnected-(TP43-Pad1)") (class "Default")
      (node (ref "TP43") (pin "1") (pintype "passive+no_connect"))
    )
    (net (code "79") (name "unconnected-(TP44-Pad1)") (class "Default")
      (node (ref "TP44") (pin "1") (pintype "passive+no_connect"))
    )
    (net (code "80") (name "unconnected-(U8-NC-Pad6)") (class "Default")
      (node (ref "U8") (pin "6") (pinfunction "NC_6") (pintype "passive+no_connect"))
    )
    (net (code "81") (name "unconnected-(U8-OCS1_N-Pad8)") (class "Default")
      (node (ref "U8") (pin "8") (pinfunction "OCS1_N_8") (pintype "passive+no_connect"))
    )
    (net (code "82") (name "unconnected-(U8-OCS2_N-Pad12)") (class "Default")
      (node (ref "U8") (pin "12") (pinfunction "OCS2_N_12") (pintype "passive+no_connect"))
    )
    (net (code "83") (name "unconnected-(U8-PLLFILT-Pad23)") (class "Default")
      (node (ref "U8") (pin "23") (pinfunction "PLLFILT_23") (pintype "passive+no_connect"))
    )
    (net (code "84") (name "unconnected-(U8-PRTPWR1{slash}(BC_EN1)-Pad7)") (class "Default")
      (node (ref "U8") (pin "7") (pinfunction "PRTPWR1/(BC_EN1)_7") (pintype "passive+no_connect"))
    )
    (net (code "85") (name "unconnected-(U8-PRTPWR2-Pad11)") (class "Default")
      (node (ref "U8") (pin "11") (pinfunction "PRTPWR2_11") (pintype "passive+no_connect"))
    )
    (net (code "86") (name "unconnected-(U9-CBUS0-Pad15)") (class "Default")
      (node (ref "U9") (pin "15") (pinfunction "CBUS0_15") (pintype "bidirectional+no_connect"))
    )
    (net (code "87") (name "unconnected-(U9-CBUS1-Pad14)") (class "Default")
      (node (ref "U9") (pin "14") (pinfunction "CBUS1_14") (pintype "bidirectional+no_connect"))
    )
    (net (code "88") (name "unconnected-(U9-CBUS2-Pad7)") (class "Default")
      (node (ref "U9") (pin "7") (pinfunction "CBUS2_7") (pintype "bidirectional+no_connect"))
    )
    (net (code "89") (name "unconnected-(U9-~{DCD}-Pad5)") (class "Default")
      (node (ref "U9") (pin "5") (pinfunction "~{DCD}_5") (pintype "input+no_connect"))
    )
    (net (code "90") (name "unconnected-(U9-~{RI}-Pad2)") (class "Default")
      (node (ref "U9") (pin "2") (pinfunction "~{RI}_2") (pintype "input+no_connect"))
    )
  )
)
